# BRD_Board_G1_v53.net
KiCad netlist of a schematic drawn in EAGLE
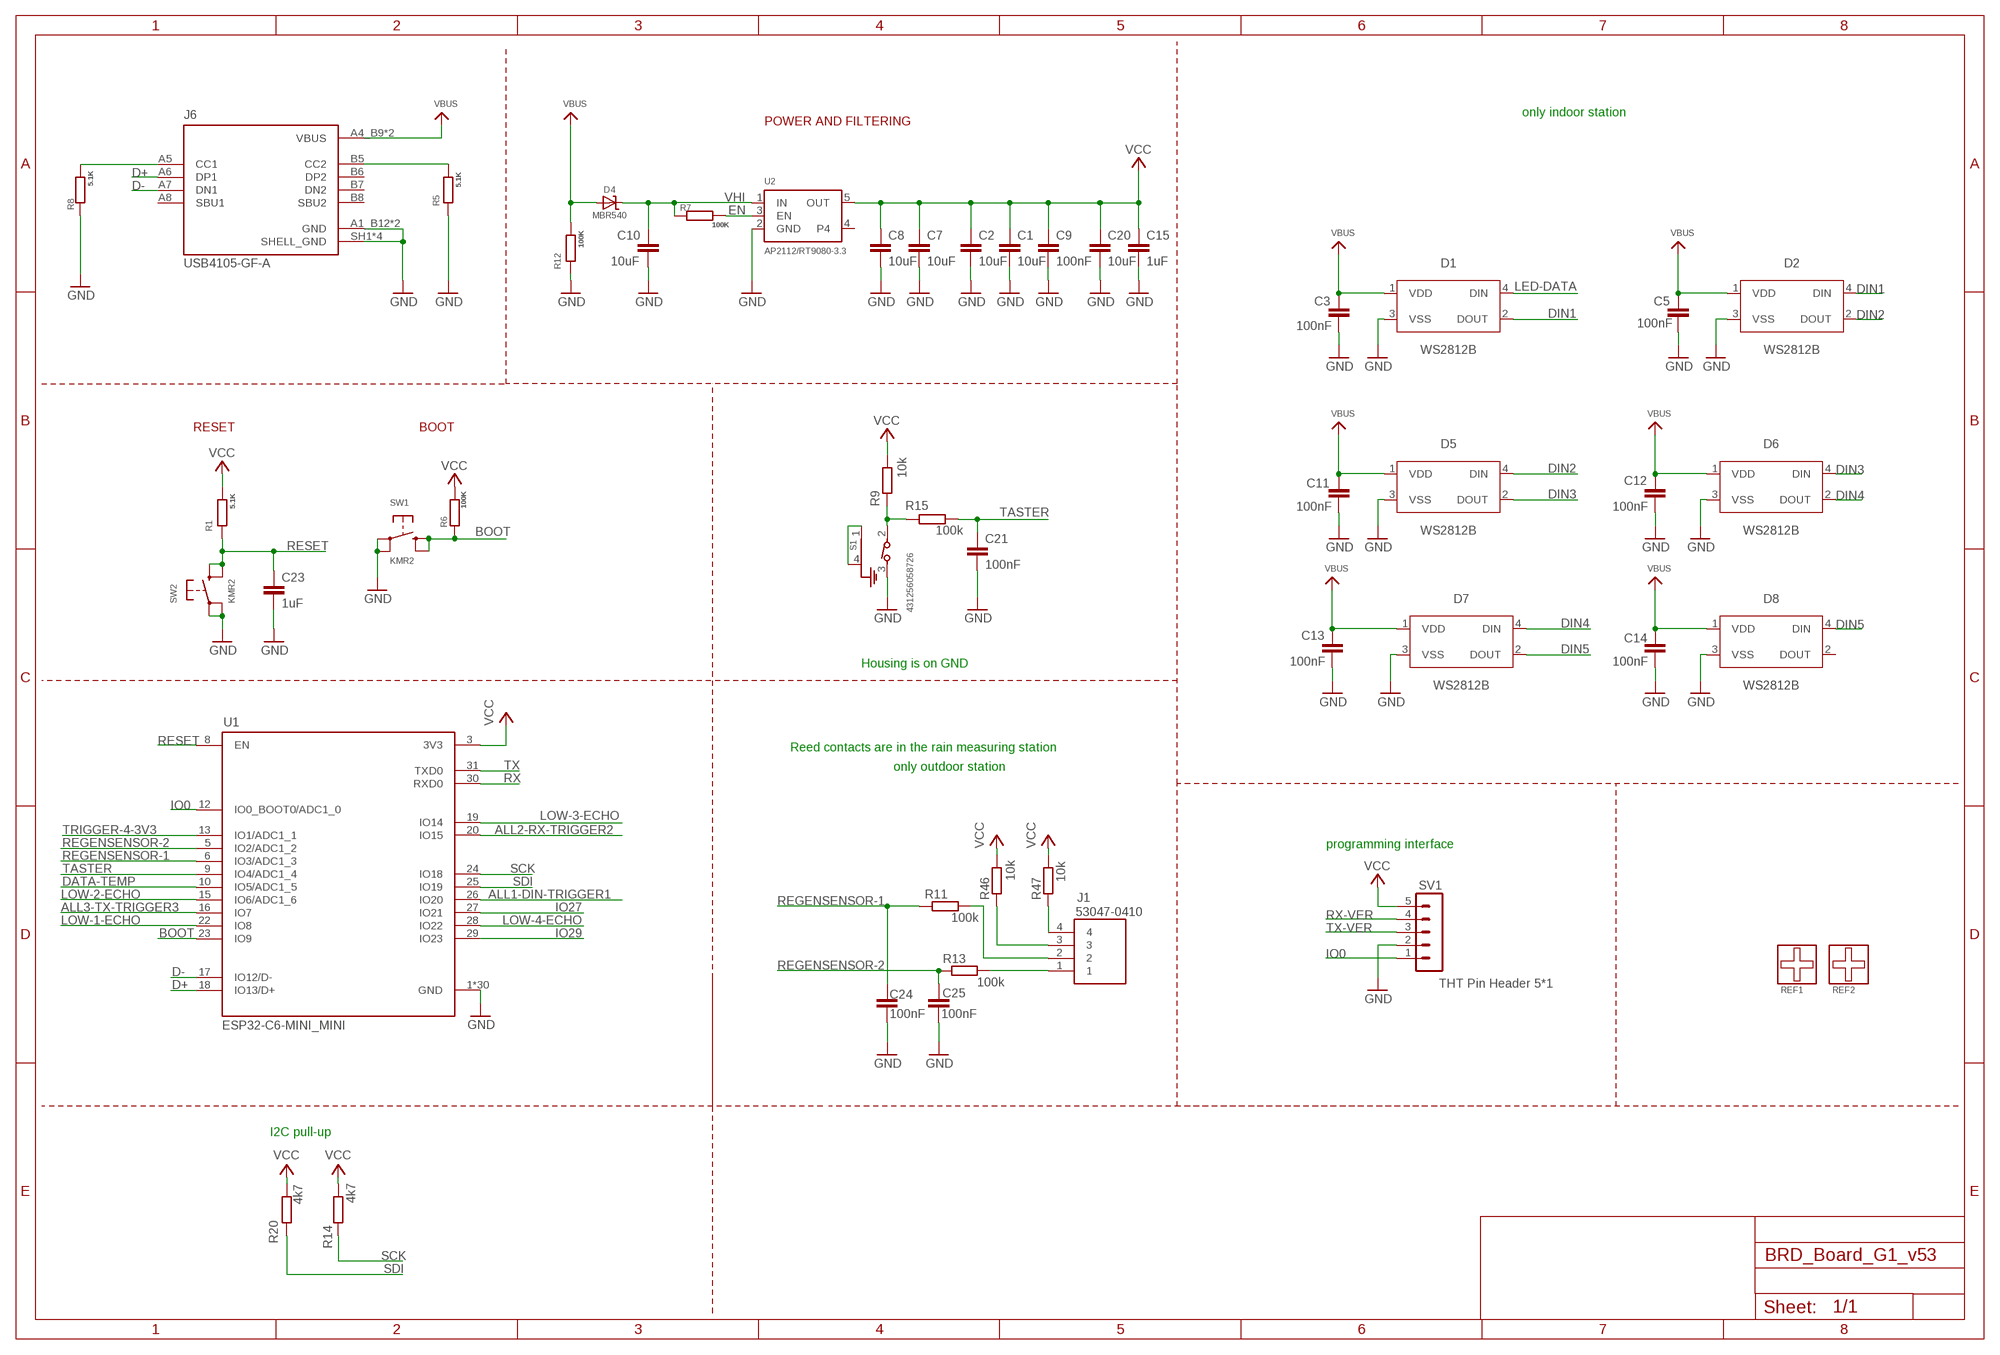
[diagram p0: schematic, sheet 1, part 1 of 2]
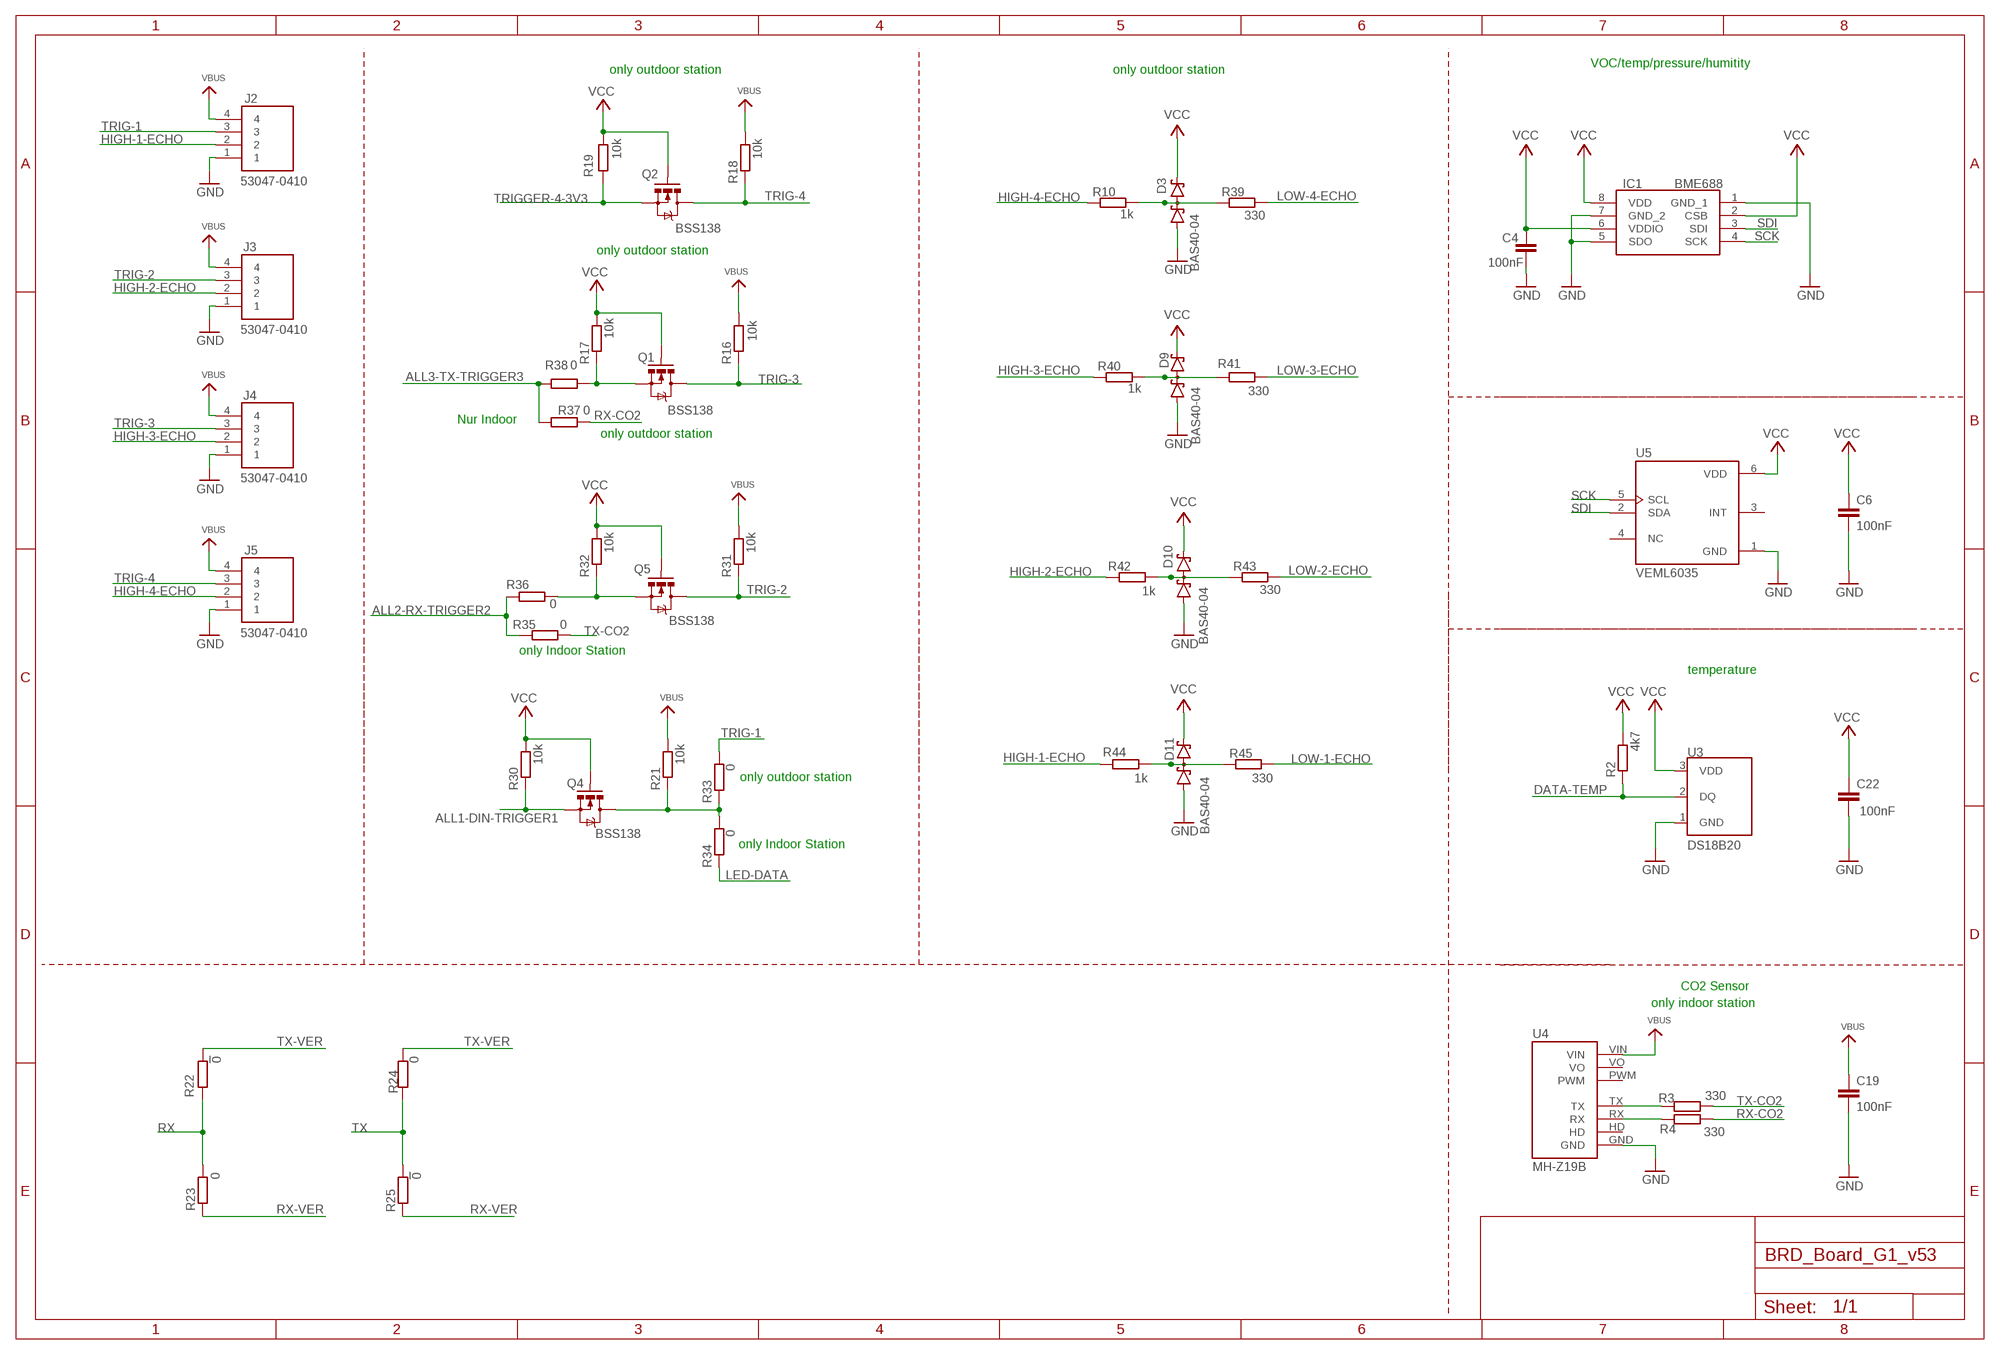
[diagram p1: schematic, sheet 1, part 2 of 2]

(export (version "E")
  (design (tool "Eeschema 10.0.6"))
  (components
    (comp (ref "C1")
      (value "10uF")
      (footprint "eagle-import:C0805K")
      (libsource (lib "eagle-import") (part "C-EUC0805K"))
    )
    (comp (ref "C2")
      (value "10uF")
      (footprint "eagle-import:C0805K")
      (libsource (lib "eagle-import") (part "C-EUC0805K"))
    )
    (comp (ref "C3")
      (value "100nF")
      (footprint "eagle-import:C0603K")
      (libsource (lib "eagle-import") (part "C-EUC0603K"))
    )
    (comp (ref "C4")
      (value "100nF")
      (footprint "eagle-import:C0603K")
      (libsource (lib "eagle-import") (part "C-EUC0603K"))
    )
    (comp (ref "C5")
      (value "100nF")
      (footprint "eagle-import:C0603K")
      (libsource (lib "eagle-import") (part "C-EUC0603K"))
    )
    (comp (ref "C6")
      (value "100nF")
      (footprint "eagle-import:C0603K")
      (libsource (lib "eagle-import") (part "C-EUC0603K"))
    )
    (comp (ref "C7")
      (value "10uF")
      (footprint "eagle-import:C0805K")
      (libsource (lib "eagle-import") (part "C-EUC0805K"))
    )
    (comp (ref "C8")
      (value "10uF")
      (footprint "eagle-import:C0805K")
      (libsource (lib "eagle-import") (part "C-EUC0805K"))
    )
    (comp (ref "C9")
      (value "100nF")
      (footprint "eagle-import:C0603K")
      (libsource (lib "eagle-import") (part "C-EUC0603K"))
    )
    (comp (ref "C10")
      (value "10uF")
      (footprint "eagle-import:C0805K")
      (libsource (lib "eagle-import") (part "C-EUC0805K"))
    )
    (comp (ref "C11")
      (value "100nF")
      (footprint "eagle-import:C0603K")
      (libsource (lib "eagle-import") (part "C-EUC0603K"))
    )
    (comp (ref "C12")
      (value "100nF")
      (footprint "eagle-import:C0603K")
      (libsource (lib "eagle-import") (part "C-EUC0603K"))
    )
    (comp (ref "C13")
      (value "100nF")
      (footprint "eagle-import:C0603K")
      (libsource (lib "eagle-import") (part "C-EUC0603K"))
    )
    (comp (ref "C14")
      (value "100nF")
      (footprint "eagle-import:C0603K")
      (libsource (lib "eagle-import") (part "C-EUC0603K"))
    )
    (comp (ref "C15")
      (value "1uF")
      (footprint "eagle-import:C0603K")
      (libsource (lib "eagle-import") (part "C-EUC0603K"))
    )
    (comp (ref "C19")
      (value "100nF")
      (footprint "eagle-import:C0603K")
      (libsource (lib "eagle-import") (part "C-EUC0603K"))
    )
    (comp (ref "C20")
      (value "10uF")
      (footprint "eagle-import:C0805K")
      (libsource (lib "eagle-import") (part "C-EUC0805K"))
    )
    (comp (ref "C21")
      (value "100nF")
      (footprint "eagle-import:C0603K")
      (libsource (lib "eagle-import") (part "C-EUC0603K"))
    )
    (comp (ref "C22")
      (value "100nF")
      (footprint "eagle-import:C0603K")
      (libsource (lib "eagle-import") (part "C-EUC0603K"))
    )
    (comp (ref "C23")
      (value "1uF")
      (footprint "eagle-import:C0805K")
      (libsource (lib "eagle-import") (part "C-EUC0805K"))
    )
    (comp (ref "C24")
      (value "100nF")
      (footprint "eagle-import:C0603K")
      (libsource (lib "eagle-import") (part "C-EUC0603K"))
    )
    (comp (ref "C25")
      (value "100nF")
      (footprint "eagle-import:C0603K")
      (libsource (lib "eagle-import") (part "C-EUC0603K"))
    )
    (comp (ref "D1")
      (value "WS2812B")
      (footprint "eagle-import:WS2812B")
      (fields (field (name "MANUFACTURER") "Worldsemi"))
      (libsource (lib "eagle-import") (part "WS2812B"))
    )
    (comp (ref "D2")
      (value "WS2812B")
      (footprint "eagle-import:WS2812B")
      (fields (field (name "MANUFACTURER") "Worldsemi"))
      (libsource (lib "eagle-import") (part "WS2812B"))
    )
    (comp (ref "D3")
      (value "BAS40-04")
      (footprint "eagle-import:SOT23")
      (libsource (lib "eagle-import") (part "BAS40-04"))
    )
    (comp (ref "D4")
      (value "MBR540")
      (footprint "eagle-import:SOD-123")
      (libsource (lib "eagle-import") (part "DIODE-SCHOTTKYSOD-123"))
    )
    (comp (ref "D5")
      (value "WS2812B")
      (footprint "eagle-import:WS2812B")
      (fields (field (name "MANUFACTURER") "Worldsemi"))
      (libsource (lib "eagle-import") (part "WS2812B"))
    )
    (comp (ref "D6")
      (value "WS2812B")
      (footprint "eagle-import:WS2812B")
      (fields (field (name "MANUFACTURER") "Worldsemi"))
      (libsource (lib "eagle-import") (part "WS2812B"))
    )
    (comp (ref "D7")
      (value "WS2812B")
      (footprint "eagle-import:WS2812B")
      (fields (field (name "MANUFACTURER") "Worldsemi"))
      (libsource (lib "eagle-import") (part "WS2812B"))
    )
    (comp (ref "D8")
      (value "WS2812B")
      (footprint "eagle-import:WS2812B")
      (fields (field (name "MANUFACTURER") "Worldsemi"))
      (libsource (lib "eagle-import") (part "WS2812B"))
    )
    (comp (ref "D9")
      (value "BAS40-04")
      (footprint "eagle-import:SOT23")
      (libsource (lib "eagle-import") (part "BAS40-04"))
    )
    (comp (ref "D10")
      (value "BAS40-04")
      (footprint "eagle-import:SOT23")
      (libsource (lib "eagle-import") (part "BAS40-04"))
    )
    (comp (ref "D11")
      (value "BAS40-04")
      (footprint "eagle-import:SOT23")
      (libsource (lib "eagle-import") (part "BAS40-04"))
    )
    (comp (ref "IC1")
      (value "BME688")
      (footprint "eagle-import:BME688")
      (fields (field (name "MOUSER_PART_NUMBER") "262-BME688"))
      (libsource (lib "eagle-import") (part "BME688"))
    )
    (comp (ref "J1")
      (value "53047-0410")
      (footprint "eagle-import:530470410")
      (fields (field (name "MOUSER_PART_NUMBER") "538-53047-0410"))
      (libsource (lib "eagle-import") (part "53047-0410"))
    )
    (comp (ref "J2")
      (value "53047-0410")
      (footprint "eagle-import:530470410")
      (fields (field (name "MOUSER_PART_NUMBER") "538-53047-0410"))
      (libsource (lib "eagle-import") (part "53047-0410"))
    )
    (comp (ref "J3")
      (value "53047-0410")
      (footprint "eagle-import:530470410")
      (fields (field (name "MOUSER_PART_NUMBER") "538-53047-0410"))
      (libsource (lib "eagle-import") (part "53047-0410"))
    )
    (comp (ref "J4")
      (value "53047-0410")
      (footprint "eagle-import:530470410")
      (fields (field (name "MOUSER_PART_NUMBER") "538-53047-0410"))
      (libsource (lib "eagle-import") (part "53047-0410"))
    )
    (comp (ref "J5")
      (value "53047-0410")
      (footprint "eagle-import:530470410")
      (fields (field (name "MOUSER_PART_NUMBER") "538-53047-0410"))
      (libsource (lib "eagle-import") (part "53047-0410"))
    )
    (comp (ref "J6")
      (value "USB4105-GF-A")
      (footprint "eagle-import:GCT_USB4105-GF-A")
      (fields (field (name "MF") "GCT"))
      (libsource (lib "eagle-import") (part "USB4105-GF-A"))
    )
    (comp (ref "Q1")
      (value "BSS138")
      (footprint "eagle-import:SOT23")
      (libsource (lib "eagle-import") (part "MOSFET-NCHANNELBSS138"))
    )
    (comp (ref "Q2")
      (value "BSS138")
      (footprint "eagle-import:SOT23")
      (libsource (lib "eagle-import") (part "MOSFET-NCHANNELBSS138"))
    )
    (comp (ref "Q4")
      (value "BSS138")
      (footprint "eagle-import:SOT23")
      (libsource (lib "eagle-import") (part "MOSFET-NCHANNELBSS138"))
    )
    (comp (ref "Q5")
      (value "BSS138")
      (footprint "eagle-import:SOT23")
      (libsource (lib "eagle-import") (part "MOSFET-NCHANNELBSS138"))
    )
    (comp (ref "R1")
      (value "5.1K")
      (footprint "eagle-import:R0805")
      (libsource (lib "eagle-import") (part "R-EU_R0805"))
    )
    (comp (ref "R2")
      (value "4k7")
      (footprint "eagle-import:R0805")
      (libsource (lib "eagle-import") (part "R-EU_R0805"))
    )
    (comp (ref "R3")
      (value "330")
      (footprint "eagle-import:R0805")
      (libsource (lib "eagle-import") (part "R-EU_R0805"))
    )
    (comp (ref "R4")
      (value "330")
      (footprint "eagle-import:R0805")
      (libsource (lib "eagle-import") (part "R-EU_R0805"))
    )
    (comp (ref "R5")
      (value "5.1K")
      (footprint "eagle-import:R0805")
      (libsource (lib "eagle-import") (part "R-EU_R0805"))
    )
    (comp (ref "R6")
      (value "100K")
      (footprint "eagle-import:R0805")
      (libsource (lib "eagle-import") (part "R-EU_R0805"))
    )
    (comp (ref "R7")
      (value "100K")
      (footprint "eagle-import:R0805")
      (libsource (lib "eagle-import") (part "R-EU_R0805"))
    )
    (comp (ref "R8")
      (value "5.1K")
      (footprint "eagle-import:R0805")
      (libsource (lib "eagle-import") (part "R-EU_R0805"))
    )
    (comp (ref "R9")
      (value "10k")
      (footprint "eagle-import:R0805")
      (libsource (lib "eagle-import") (part "R-EU_R0805"))
    )
    (comp (ref "R10")
      (value "1k")
      (footprint "eagle-import:R0805")
      (libsource (lib "eagle-import") (part "R-EU_R0805"))
    )
    (comp (ref "R11")
      (value "100k")
      (footprint "eagle-import:R0805")
      (libsource (lib "eagle-import") (part "R-EU_R0805"))
    )
    (comp (ref "R12")
      (value "100K")
      (footprint "eagle-import:R0805")
      (libsource (lib "eagle-import") (part "R-EU_R0805"))
    )
    (comp (ref "R13")
      (value "100k")
      (footprint "eagle-import:R0805")
      (libsource (lib "eagle-import") (part "R-EU_R0805"))
    )
    (comp (ref "R14")
      (value "4k7")
      (footprint "eagle-import:R0805")
      (libsource (lib "eagle-import") (part "R-EU_R0805"))
    )
    (comp (ref "R15")
      (value "100k")
      (footprint "eagle-import:R0805")
      (libsource (lib "eagle-import") (part "R-EU_R0805"))
    )
    (comp (ref "R16")
      (value "10k")
      (footprint "eagle-import:R0805")
      (libsource (lib "eagle-import") (part "R-EU_R0805"))
    )
    (comp (ref "R17")
      (value "10k")
      (footprint "eagle-import:R0805")
      (libsource (lib "eagle-import") (part "R-EU_R0805"))
    )
    (comp (ref "R18")
      (value "10k")
      (footprint "eagle-import:R0805")
      (libsource (lib "eagle-import") (part "R-EU_R0805"))
    )
    (comp (ref "R19")
      (value "10k")
      (footprint "eagle-import:R0805")
      (libsource (lib "eagle-import") (part "R-EU_R0805"))
    )
    (comp (ref "R20")
      (value "4k7")
      (footprint "eagle-import:R0805")
      (libsource (lib "eagle-import") (part "R-EU_R0805"))
    )
    (comp (ref "R21")
      (value "10k")
      (footprint "eagle-import:R0805")
      (libsource (lib "eagle-import") (part "R-EU_R0805"))
    )
    (comp (ref "R22")
      (value "!0")
      (footprint "eagle-import:R0805")
      (libsource (lib "eagle-import") (part "R-EU_R0805"))
    )
    (comp (ref "R23")
      (value "0")
      (footprint "eagle-import:R0805")
      (libsource (lib "eagle-import") (part "R-EU_R0805"))
    )
    (comp (ref "R24")
      (value "0")
      (footprint "eagle-import:R0805")
      (libsource (lib "eagle-import") (part "R-EU_R0805"))
    )
    (comp (ref "R25")
      (value "!0")
      (footprint "eagle-import:R0805")
      (libsource (lib "eagle-import") (part "R-EU_R0805"))
    )
    (comp (ref "R30")
      (value "10k")
      (footprint "eagle-import:R0805")
      (libsource (lib "eagle-import") (part "R-EU_R0805"))
    )
    (comp (ref "R31")
      (value "10k")
      (footprint "eagle-import:R0805")
      (libsource (lib "eagle-import") (part "R-EU_R0805"))
    )
    (comp (ref "R32")
      (value "10k")
      (footprint "eagle-import:R0805")
      (libsource (lib "eagle-import") (part "R-EU_R0805"))
    )
    (comp (ref "R33")
      (value "0")
      (footprint "eagle-import:R0805")
      (libsource (lib "eagle-import") (part "R-EU_R0805"))
    )
    (comp (ref "R34")
      (value "0")
      (footprint "eagle-import:R0805")
      (libsource (lib "eagle-import") (part "R-EU_R0805"))
    )
    (comp (ref "R35")
      (value "0")
      (footprint "eagle-import:R0805")
      (libsource (lib "eagle-import") (part "R-EU_R0805"))
    )
    (comp (ref "R36")
      (value "0")
      (footprint "eagle-import:R0805")
      (libsource (lib "eagle-import") (part "R-EU_R0805"))
    )
    (comp (ref "R37")
      (value "0")
      (footprint "eagle-import:R0805")
      (libsource (lib "eagle-import") (part "R-EU_R0805"))
    )
    (comp (ref "R38")
      (value "0")
      (footprint "eagle-import:R0805")
      (libsource (lib "eagle-import") (part "R-EU_R0805"))
    )
    (comp (ref "R39")
      (value "330")
      (footprint "eagle-import:R0805")
      (libsource (lib "eagle-import") (part "R-EU_R0805"))
    )
    (comp (ref "R40")
      (value "1k")
      (footprint "eagle-import:R0805")
      (libsource (lib "eagle-import") (part "R-EU_R0805"))
    )
    (comp (ref "R41")
      (value "330")
      (footprint "eagle-import:R0805")
      (libsource (lib "eagle-import") (part "R-EU_R0805"))
    )
    (comp (ref "R42")
      (value "1k")
      (footprint "eagle-import:R0805")
      (libsource (lib "eagle-import") (part "R-EU_R0805"))
    )
    (comp (ref "R43")
      (value "330")
      (footprint "eagle-import:R0805")
      (libsource (lib "eagle-import") (part "R-EU_R0805"))
    )
    (comp (ref "R44")
      (value "1k")
      (footprint "eagle-import:R0805")
      (libsource (lib "eagle-import") (part "R-EU_R0805"))
    )
    (comp (ref "R45")
      (value "330")
      (footprint "eagle-import:R0805")
      (libsource (lib "eagle-import") (part "R-EU_R0805"))
    )
    (comp (ref "R46")
      (value "10k")
      (footprint "eagle-import:R0805")
      (libsource (lib "eagle-import") (part "R-EU_R0805"))
    )
    (comp (ref "R47")
      (value "10k")
      (footprint "eagle-import:R0805")
      (libsource (lib "eagle-import") (part "R-EU_R0805"))
    )
    (comp (ref "REF1")
      (value "FIDUCIALFIDU_1_3_MM")
      (footprint "eagle-import:FIDU_1_3MM")
      (libsource (lib "eagle-import") (part "FIDUCIALFIDU_1_3_MM"))
    )
    (comp (ref "REF2")
      (value "FIDUCIALFIDU_1_3_MM")
      (footprint "eagle-import:FIDU_1_3MM")
      (libsource (lib "eagle-import") (part "FIDUCIALFIDU_1_3_MM"))
    )
    (comp (ref "S1")
      (value "431256058726")
      (footprint "eagle-import:4312560587X6")
      (fields (field (name "MF") "Würth Elektronik") (field (name "MP") "431256058716"))
      (libsource (lib "eagle-import") (part "431256058726"))
    )
    (comp (ref "SV1")
      (value "THT Pin Header 5*1")
      (footprint "eagle-import:MAR05-1")
      (libsource (lib "eagle-import") (part "MAR05-1"))
    )
    (comp (ref "SW1")
      (value "KMR2")
      (footprint "eagle-import:BTN_RKB2_4.6X2.8")
      (libsource (lib "eagle-import") (part "SWITCH_TACT_SMT_RKB2"))
    )
    (comp (ref "SW2")
      (value "KMR2")
      (footprint "eagle-import:BTN_RKB2_4.6X2.8")
      (libsource (lib "eagle-import") (part "SWITCH_TACT_SMT_RKB2"))
    )
    (comp (ref "U1")
      (value "ESP32-C6-MINI_MINI")
      (footprint "eagle-import:ESP32-PICO-MINI")
      (libsource (lib "eagle-import") (part "ESP32-C6-MINI_MINI"))
    )
    (comp (ref "U2")
      (value "AP2112/RT9080-3.3")
      (footprint "eagle-import:SOT23-5")
      (fields (field (name "JLC_ROTATION") "0"))
      (libsource (lib "eagle-import") (part "VREG_SOT23-5"))
    )
    (comp (ref "U3")
      (value "DS18B20")
      (footprint "eagle-import:TO-92-AMMO")
      (libsource (lib "eagle-import") (part "DS18B20"))
    )
    (comp (ref "U4")
      (value "MH-Z19B")
      (footprint "eagle-import:MH-Z19B")
      (fields (field (name "MF") "Winsen"))
      (libsource (lib "eagle-import") (part "MH-Z19B"))
    )
    (comp (ref "U5")
      (value "VEML6035")
      (footprint "eagle-import:XDCR_VEML6035")
      (fields (field (name "MF") "Vishay Semiconductor Opto Division"))
      (libsource (lib "eagle-import") (part "VEML6035"))
    )
  )
  (nets
    (net (code "1") (name "/ALL1-DIN-TRIGGER1") (class "Default")
      (node (ref "Q4") (pin "2") (pinfunction "S_2") (pintype "passive"))
      (node (ref "R30") (pin "1") (pinfunction "1_1") (pintype "passive"))
      (node (ref "U1") (pin "26") (pinfunction "IO20_26") (pintype "bidirectional"))
    )
    (net (code "2") (name "/ALL2-RX-TRIGGER2") (class "Default")
      (node (ref "R35") (pin "1") (pinfunction "1_1") (pintype "passive"))
      (node (ref "R36") (pin "1") (pinfunction "1_1") (pintype "passive"))
      (node (ref "U1") (pin "20") (pinfunction "IO15_20") (pintype "bidirectional"))
    )
    (net (code "3") (name "/ALL3-TX-TRIGGER3") (class "Default")
      (node (ref "R37") (pin "1") (pinfunction "1_1") (pintype "passive"))
      (node (ref "R38") (pin "1") (pinfunction "1_1") (pintype "passive"))
      (node (ref "U1") (pin "16") (pinfunction "IO7_16") (pintype "bidirectional"))
    )
    (net (code "4") (name "/BOOT") (class "Default")
      (node (ref "R6") (pin "1") (pinfunction "1_1") (pintype "passive"))
      (node (ref "SW1") (pin "B") (pinfunction "S_B") (pintype "passive"))
      (node (ref "SW1") (pin "B'") (pinfunction "S1_B'") (pintype "passive"))
      (node (ref "U1") (pin "23") (pinfunction "IO9_23") (pintype "bidirectional"))
    )
    (net (code "5") (name "/D+") (class "Default")
      (node (ref "J6") (pin "A6") (pinfunction "DP1_A6") (pintype "bidirectional"))
      (node (ref "U1") (pin "18") (pinfunction "IO13/D+_18") (pintype "bidirectional"))
    )
    (net (code "6") (name "/D-") (class "Default")
      (node (ref "J6") (pin "A7") (pinfunction "DN1_A7") (pintype "bidirectional"))
      (node (ref "U1") (pin "17") (pinfunction "IO12/D-_17") (pintype "bidirectional"))
    )
    (net (code "7") (name "/DATA-TEMP") (class "Default")
      (node (ref "R2") (pin "1") (pinfunction "1_1") (pintype "passive"))
      (node (ref "U1") (pin "10") (pinfunction "IO5/ADC1_5_10") (pintype "bidirectional"))
      (node (ref "U3") (pin "2") (pinfunction "DQ_2") (pintype "bidirectional"))
    )
    (net (code "8") (name "/DIN1") (class "Default")
      (node (ref "D1") (pin "2") (pinfunction "DOUT_2") (pintype "output"))
      (node (ref "D2") (pin "4") (pinfunction "DIN_4") (pintype "input"))
    )
    (net (code "9") (name "/DIN2") (class "Default")
      (node (ref "D2") (pin "2") (pinfunction "DOUT_2") (pintype "output"))
      (node (ref "D5") (pin "4") (pinfunction "DIN_4") (pintype "input"))
    )
    (net (code "10") (name "/DIN3") (class "Default")
      (node (ref "D5") (pin "2") (pinfunction "DOUT_2") (pintype "output"))
      (node (ref "D6") (pin "4") (pinfunction "DIN_4") (pintype "input"))
    )
    (net (code "11") (name "/DIN4") (class "Default")
      (node (ref "D6") (pin "2") (pinfunction "DOUT_2") (pintype "output"))
      (node (ref "D7") (pin "4") (pinfunction "DIN_4") (pintype "input"))
    )
    (net (code "12") (name "/DIN5") (class "Default")
      (node (ref "D7") (pin "2") (pinfunction "DOUT_2") (pintype "output"))
      (node (ref "D8") (pin "4") (pinfunction "DIN_4") (pintype "input"))
    )
    (net (code "13") (name "/EN") (class "Default")
      (node (ref "R7") (pin "1") (pinfunction "1_1") (pintype "passive"))
      (node (ref "U2") (pin "3") (pinfunction "EN_3") (pintype "input"))
    )
    (net (code "14") (name "/HIGH-1-ECHO") (class "Default")
      (node (ref "J2") (pin "2") (pinfunction "2_2") (pintype "bidirectional"))
      (node (ref "R44") (pin "2") (pinfunction "2_2") (pintype "passive"))
    )
    (net (code "15") (name "/HIGH-2-ECHO") (class "Default")
      (node (ref "J3") (pin "2") (pinfunction "2_2") (pintype "bidirectional"))
      (node (ref "R42") (pin "2") (pinfunction "2_2") (pintype "passive"))
    )
    (net (code "16") (name "/HIGH-3-ECHO") (class "Default")
      (node (ref "J4") (pin "2") (pinfunction "2_2") (pintype "bidirectional"))
      (node (ref "R40") (pin "2") (pinfunction "2_2") (pintype "passive"))
    )
    (net (code "17") (name "/HIGH-4-ECHO") (class "Default")
      (node (ref "J5") (pin "2") (pinfunction "2_2") (pintype "bidirectional"))
      (node (ref "R10") (pin "2") (pinfunction "2_2") (pintype "passive"))
    )
    (net (code "18") (name "/IO0") (class "Default")
      (node (ref "SV1") (pin "1") (pinfunction "1_1") (pintype "passive"))
      (node (ref "U1") (pin "12") (pinfunction "IO0_BOOT0/ADC1_0_12") (pintype "bidirectional"))
    )
    (net (code "19") (name "/IO27") (class "Default")
      (node (ref "U1") (pin "27") (pinfunction "IO21_27") (pintype "bidirectional"))
    )
    (net (code "20") (name "/IO29") (class "Default")
      (node (ref "U1") (pin "29") (pinfunction "IO23_29") (pintype "bidirectional"))
    )
    (net (code "21") (name "/LED-DATA") (class "Default")
      (node (ref "D1") (pin "4") (pinfunction "DIN_4") (pintype "input"))
      (node (ref "R34") (pin "1") (pinfunction "1_1") (pintype "passive"))
    )
    (net (code "22") (name "/LOW-1-ECHO") (class "Default")
      (node (ref "R45") (pin "1") (pinfunction "1_1") (pintype "passive"))
      (node (ref "U1") (pin "22") (pinfunction "IO8_22") (pintype "bidirectional"))
    )
    (net (code "23") (name "/LOW-2-ECHO") (class "Default")
      (node (ref "R43") (pin "1") (pinfunction "1_1") (pintype "passive"))
      (node (ref "U1") (pin "15") (pinfunction "IO6/ADC1_6_15") (pintype "bidirectional"))
    )
    (net (code "24") (name "/LOW-3-ECHO") (class "Default")
      (node (ref "R41") (pin "1") (pinfunction "1_1") (pintype "passive"))
      (node (ref "U1") (pin "19") (pinfunction "IO14_19") (pintype "bidirectional"))
    )
    (net (code "25") (name "/LOW-4-ECHO") (class "Default")
      (node (ref "R39") (pin "1") (pinfunction "1_1") (pintype "passive"))
      (node (ref "U1") (pin "28") (pinfunction "IO22_28") (pintype "bidirectional"))
    )
    (net (code "26") (name "/REGENSENSOR-1") (class "Default")
      (node (ref "C24") (pin "1") (pinfunction "1_1") (pintype "passive"))
      (node (ref "R11") (pin "2") (pinfunction "2_2") (pintype "passive"))
      (node (ref "U1") (pin "6") (pinfunction "IO3/ADC1_3_6") (pintype "bidirectional"))
    )
    (net (code "27") (name "/REGENSENSOR-2") (class "Default")
      (node (ref "C25") (pin "1") (pinfunction "1_1") (pintype "passive"))
      (node (ref "R13") (pin "2") (pinfunction "2_2") (pintype "passive"))
      (node (ref "U1") (pin "5") (pinfunction "IO2/ADC1_2_5") (pintype "bidirectional"))
    )
    (net (code "28") (name "/RESET") (class "Default")
      (node (ref "C23") (pin "1") (pinfunction "1_1") (pintype "passive"))
      (node (ref "R1") (pin "1") (pinfunction "1_1") (pintype "passive"))
      (node (ref "SW2") (pin "B") (pinfunction "S_B") (pintype "passive"))
      (node (ref "SW2") (pin "B'") (pinfunction "S1_B'") (pintype "passive"))
      (node (ref "U1") (pin "8") (pinfunction "EN_8") (pintype "input"))
    )
    (net (code "29") (name "/RX") (class "Default")
      (node (ref "R22") (pin "2") (pinfunction "2_2") (pintype "passive"))
      (node (ref "R23") (pin "1") (pinfunction "1_1") (pintype "passive"))
      (node (ref "U1") (pin "30") (pinfunction "RXD0_30") (pintype "bidirectional"))
    )
    (net (code "30") (name "/RX-CO2") (class "Default")
      (node (ref "R37") (pin "2") (pinfunction "2_2") (pintype "passive"))
      (node (ref "R4") (pin "1") (pinfunction "1_1") (pintype "passive"))
    )
    (net (code "31") (name "/RX-VER") (class "Default")
      (node (ref "R23") (pin "2") (pinfunction "2_2") (pintype "passive"))
      (node (ref "R25") (pin "2") (pinfunction "2_2") (pintype "passive"))
      (node (ref "SV1") (pin "4") (pinfunction "4_4") (pintype "passive"))
    )
    (net (code "32") (name "/SCK") (class "Default")
      (node (ref "IC1") (pin "4") (pinfunction "SCK_4") (pintype "bidirectional"))
      (node (ref "R14") (pin "1") (pinfunction "1_1") (pintype "passive"))
      (node (ref "U1") (pin "24") (pinfunction "IO18_24") (pintype "bidirectional"))
      (node (ref "U5") (pin "5") (pinfunction "SCL_5") (pintype "input"))
    )
    (net (code "33") (name "/SDI") (class "Default")
      (node (ref "IC1") (pin "3") (pinfunction "SDI_3") (pintype "bidirectional"))
      (node (ref "R20") (pin "1") (pinfunction "1_1") (pintype "passive"))
      (node (ref "U1") (pin "25") (pinfunction "IO19_25") (pintype "bidirectional"))
      (node (ref "U5") (pin "2") (pinfunction "SDA_2") (pintype "bidirectional"))
    )
    (net (code "34") (name "/TASTER") (class "Default")
      (node (ref "C21") (pin "1") (pinfunction "1_1") (pintype "passive"))
      (node (ref "R15") (pin "1") (pinfunction "1_1") (pintype "passive"))
      (node (ref "U1") (pin "9") (pinfunction "IO4/ADC1_4_9") (pintype "bidirectional"))
    )
    (net (code "35") (name "/TRIG-1") (class "Default")
      (node (ref "J2") (pin "3") (pinfunction "3_3") (pintype "bidirectional"))
      (node (ref "R33") (pin "2") (pinfunction "2_2") (pintype "passive"))
    )
    (net (code "36") (name "/TRIG-2") (class "Default")
      (node (ref "J3") (pin "3") (pinfunction "3_3") (pintype "bidirectional"))
      (node (ref "Q5") (pin "3") (pinfunction "D_3") (pintype "passive"))
      (node (ref "R31") (pin "1") (pinfunction "1_1") (pintype "passive"))
    )
    (net (code "37") (name "/TRIG-3") (class "Default")
      (node (ref "J4") (pin "3") (pinfunction "3_3") (pintype "bidirectional"))
      (node (ref "Q1") (pin "3") (pinfunction "D_3") (pintype "passive"))
      (node (ref "R16") (pin "1") (pinfunction "1_1") (pintype "passive"))
    )
    (net (code "38") (name "/TRIG-4") (class "Default")
      (node (ref "J5") (pin "3") (pinfunction "3_3") (pintype "bidirectional"))
      (node (ref "Q2") (pin "3") (pinfunction "D_3") (pintype "passive"))
      (node (ref "R18") (pin "1") (pinfunction "1_1") (pintype "passive"))
    )
    (net (code "39") (name "/TRIGGER-4-3V3") (class "Default")
      (node (ref "Q2") (pin "2") (pinfunction "S_2") (pintype "passive"))
      (node (ref "R19") (pin "1") (pinfunction "1_1") (pintype "passive"))
      (node (ref "U1") (pin "13") (pinfunction "IO1/ADC1_1_13") (pintype "bidirectional"))
    )
    (net (code "40") (name "/TX") (class "Default")
      (node (ref "R24") (pin "2") (pinfunction "2_2") (pintype "passive"))
      (node (ref "R25") (pin "1") (pinfunction "1_1") (pintype "passive"))
      (node (ref "U1") (pin "31") (pinfunction "TXD0_31") (pintype "bidirectional"))
    )
    (net (code "41") (name "/TX-CO2") (class "Default")
      (node (ref "R3") (pin "1") (pinfunction "1_1") (pintype "passive"))
      (node (ref "R35") (pin "2") (pinfunction "2_2") (pintype "passive"))
    )
    (net (code "42") (name "/TX-VER") (class "Default")
      (node (ref "R22") (pin "1") (pinfunction "1_1") (pintype "passive"))
      (node (ref "R24") (pin "1") (pinfunction "1_1") (pintype "passive"))
      (node (ref "SV1") (pin "3") (pinfunction "3_3") (pintype "passive"))
    )
    (net (code "43") (name "/VHI") (class "Default")
      (node (ref "C10") (pin "1") (pinfunction "1_1") (pintype "passive"))
      (node (ref "D4") (pin "C") (pinfunction "C_C") (pintype "passive"))
      (node (ref "R7") (pin "2") (pinfunction "2_2") (pintype "passive"))
      (node (ref "U2") (pin "1") (pinfunction "IN_1") (pintype "power_in"))
    )
    (net (code "44") (name "GND") (class "Default")
      (node (ref "C1") (pin "2") (pinfunction "2_2") (pintype "passive"))
      (node (ref "C10") (pin "2") (pinfunction "2_2") (pintype "passive"))
      (node (ref "C11") (pin "2") (pinfunction "2_2") (pintype "passive"))
      (node (ref "C12") (pin "2") (pinfunction "2_2") (pintype "passive"))
      (node (ref "C13") (pin "2") (pinfunction "2_2") (pintype "passive"))
      (node (ref "C14") (pin "2") (pinfunction "2_2") (pintype "passive"))
      (node (ref "C15") (pin "2") (pinfunction "2_2") (pintype "passive"))
      (node (ref "C19") (pin "2") (pinfunction "2_2") (pintype "passive"))
      (node (ref "C2") (pin "2") (pinfunction "2_2") (pintype "passive"))
      (node (ref "C20") (pin "2") (pinfunction "2_2") (pintype "passive"))
      (node (ref "C21") (pin "2") (pinfunction "2_2") (pintype "passive"))
      (node (ref "C22") (pin "1") (pinfunction "1_1") (pintype "passive"))
      (node (ref "C23") (pin "2") (pinfunction "2_2") (pintype "passive"))
      (node (ref "C24") (pin "2") (pinfunction "2_2") (pintype "passive"))
      (node (ref "C25") (pin "2") (pinfunction "2_2") (pintype "passive"))
      (node (ref "C3") (pin "2") (pinfunction "2_2") (pintype "passive"))
      (node (ref "C4") (pin "1") (pinfunction "1_1") (pintype "passive"))
      (node (ref "C5") (pin "2") (pinfunction "2_2") (pintype "passive"))
      (node (ref "C6") (pin "2") (pinfunction "2_2") (pintype "passive"))
      (node (ref "C7") (pin "2") (pinfunction "2_2") (pintype "passive"))
      (node (ref "C8") (pin "2") (pinfunction "2_2") (pintype "passive"))
      (node (ref "C9") (pin "2") (pinfunction "2_2") (pintype "passive"))
      (node (ref "D1") (pin "3") (pinfunction "VSS_3") (pintype "power_in"))
      (node (ref "D10") (pin "1") (pinfunction "A1_1") (pintype "passive"))
      (node (ref "D11") (pin "1") (pinfunction "A1_1") (pintype "passive"))
      (node (ref "D2") (pin "3") (pinfunction "VSS_3") (pintype "power_in"))
      (node (ref "D3") (pin "1") (pinfunction "A1_1") (pintype "passive"))
      (node (ref "D5") (pin "3") (pinfunction "VSS_3") (pintype "power_in"))
      (node (ref "D6") (pin "3") (pinfunction "VSS_3") (pintype "power_in"))
      (node (ref "D7") (pin "3") (pinfunction "VSS_3") (pintype "power_in"))
      (node (ref "D8") (pin "3") (pinfunction "VSS_3") (pintype "power_in"))
      (node (ref "D9") (pin "1") (pinfunction "A1_1") (pintype "passive"))
      (node (ref "IC1") (pin "1") (pinfunction "GND_1_1") (pintype "bidirectional"))
      (node (ref "IC1") (pin "5") (pinfunction "SDO_5") (pintype "bidirectional"))
      (node (ref "IC1") (pin "7") (pinfunction "GND_2_7") (pintype "bidirectional"))
      (node (ref "J2") (pin "1") (pinfunction "1_1") (pintype "bidirectional"))
      (node (ref "J3") (pin "1") (pinfunction "1_1") (pintype "bidirectional"))
      (node (ref "J4") (pin "1") (pinfunction "1_1") (pintype "bidirectional"))
      (node (ref "J5") (pin "1") (pinfunction "1_1") (pintype "bidirectional"))
      (node (ref "J6") (pin "A1_B12") (pinfunction "GND_A1_B12") (pintype "power_in"))
      (node (ref "J6") (pin "B1_A12") (pinfunction "GND_B1_A12") (pintype "power_in"))
      (node (ref "J6") (pin "SH1") (pinfunction "SHELL_GND_SH1") (pintype "power_in"))
      (node (ref "J6") (pin "SH2") (pinfunction "SHELL_GND_SH2") (pintype "power_in"))
      (node (ref "J6") (pin "SH3") (pinfunction "SHELL_GND_SH3") (pintype "power_in"))
      (node (ref "J6") (pin "SH4") (pinfunction "SHELL_GND_SH4") (pintype "power_in"))
      (node (ref "R12") (pin "1") (pinfunction "1_1") (pintype "passive"))
      (node (ref "R5") (pin "1") (pinfunction "1_1") (pintype "passive"))
      (node (ref "R8") (pin "1") (pinfunction "1_1") (pintype "passive"))
      (node (ref "S1") (pin "3") (pinfunction "3_3") (pintype "passive"))
      (node (ref "SV1") (pin "2") (pinfunction "2_2") (pintype "passive"))
      (node (ref "SW1") (pin "A") (pinfunction "P_A") (pintype "passive"))
      (node (ref "SW1") (pin "A'") (pinfunction "P1_A'") (pintype "passive"))
      (node (ref "SW2") (pin "A") (pinfunction "P_A") (pintype "passive"))
      (node (ref "SW2") (pin "A'") (pinfunction "P1_A'") (pintype "passive"))
      (node (ref "U1") (pin "1") (pinfunction "GND_1") (pintype "power_in"))
      (node (ref "U1") (pin "11") (pinfunction "GND_11") (pintype "power_in"))
      (node (ref "U1") (pin "14") (pinfunction "GND_14") (pintype "power_in"))
      (node (ref "U1") (pin "2") (pinfunction "GND_2") (pintype "power_in"))
      (node (ref "U1") (pin "36") (pinfunction "GND_36") (pintype "power_in"))
      (node (ref "U1") (pin "37") (pinfunction "GND_37") (pintype "power_in"))
      (node (ref "U1") (pin "38") (pinfunction "GND_38") (pintype "power_in"))
      (node (ref "U1") (pin "39") (pinfunction "GND_39") (pintype "power_in"))
      (node (ref "U1") (pin "40") (pinfunction "GND_40") (pintype "power_in"))
      (node (ref "U1") (pin "41") (pinfunction "GND_41") (pintype "power_in"))
      (node (ref "U1") (pin "42") (pinfunction "GND_42") (pintype "power_in"))
      (node (ref "U1") (pin "43") (pinfunction "GND_43") (pintype "power_in"))
      (node (ref "U1") (pin "44") (pinfunction "GND_44") (pintype "power_in"))
      (node (ref "U1") (pin "45") (pinfunction "GND_45") (pintype "power_in"))
      (node (ref "U1") (pin "46") (pinfunction "GND_46") (pintype "power_in"))
      (node (ref "U1") (pin "47") (pinfunction "GND_47") (pintype "power_in"))
      (node (ref "U1") (pin "48") (pinfunction "GND_48") (pintype "power_in"))
      (node (ref "U1") (pin "49") (pinfunction "GND_49") (pintype "power_in"))
      (node (ref "U1") (pin "50") (pinfunction "GND_50") (pintype "power_in"))
      (node (ref "U1") (pin "51") (pinfunction "GND_51") (pintype "power_in"))
      (node (ref "U1") (pin "52") (pinfunction "GND_52") (pintype "power_in"))
      (node (ref "U1") (pin "53") (pinfunction "GND_53") (pintype "power_in"))
      (node (ref "U1") (pin "54") (pinfunction "GND_54") (pintype "power_in"))
      (node (ref "U1") (pin "55") (pinfunction "GND_55") (pintype "power_in"))
      (node (ref "U1") (pin "56") (pinfunction "GND_56") (pintype "power_in"))
      (node (ref "U1") (pin "57") (pinfunction "GND_57") (pintype "power_in"))
      (node (ref "U1") (pin "58") (pinfunction "GND_58") (pintype "power_in"))
      (node (ref "U1") (pin "59") (pinfunction "GND_59") (pintype "power_in"))
      (node (ref "U1") (pin "60") (pinfunction "GND_60") (pintype "power_in"))
      (node (ref "U1") (pin "61") (pinfunction "GND_61") (pintype "power_in"))
      (node (ref "U2") (pin "2") (pinfunction "GND_2") (pintype "power_in"))
      (node (ref "U3") (pin "1") (pinfunction "GND_1") (pintype "power_in"))
      (node (ref "U4") (pin "GND") (pinfunction "GND_GND") (pintype "bidirectional"))
      (node (ref "U5") (pin "1") (pinfunction "GND_1") (pintype "power_in"))
    )
    (net (code "45") (name "Net-(D3-C1A2)") (class "Default")
      (node (ref "D3") (pin "3") (pinfunction "C1A2_3") (pintype "passive"))
      (node (ref "R10") (pin "1") (pinfunction "1_1") (pintype "passive"))
      (node (ref "R39") (pin "2") (pinfunction "2_2") (pintype "passive"))
    )
    (net (code "46") (name "Net-(D9-C1A2)") (class "Default")
      (node (ref "D9") (pin "3") (pinfunction "C1A2_3") (pintype "passive"))
      (node (ref "R40") (pin "1") (pinfunction "1_1") (pintype "passive"))
      (node (ref "R41") (pin "2") (pinfunction "2_2") (pintype "passive"))
    )
    (net (code "47") (name "Net-(D10-C1A2)") (class "Default")
      (node (ref "D10") (pin "3") (pinfunction "C1A2_3") (pintype "passive"))
      (node (ref "R42") (pin "1") (pinfunction "1_1") (pintype "passive"))
      (node (ref "R43") (pin "2") (pinfunction "2_2") (pintype "passive"))
    )
    (net (code "48") (name "Net-(D11-C1A2)") (class "Default")
      (node (ref "D11") (pin "3") (pinfunction "C1A2_3") (pintype "passive"))
      (node (ref "R44") (pin "1") (pinfunction "1_1") (pintype "passive"))
      (node (ref "R45") (pin "2") (pinfunction "2_2") (pintype "passive"))
    )
    (net (code "49") (name "Net-(J1-Pad1)") (class "Default")
      (node (ref "J1") (pin "1") (pinfunction "1_1") (pintype "bidirectional"))
      (node (ref "R13") (pin "1") (pinfunction "1_1") (pintype "passive"))
    )
    (net (code "50") (name "Net-(J1-Pad2)") (class "Default")
      (node (ref "J1") (pin "2") (pinfunction "2_2") (pintype "bidirectional"))
      (node (ref "R11") (pin "1") (pinfunction "1_1") (pintype "passive"))
    )
    (net (code "51") (name "Net-(J1-Pad3)") (class "Default")
      (node (ref "J1") (pin "3") (pinfunction "3_3") (pintype "bidirectional"))
      (node (ref "R46") (pin "1") (pinfunction "1_1") (pintype "passive"))
    )
    (net (code "52") (name "Net-(J1-Pad4)") (class "Default")
      (node (ref "J1") (pin "4") (pinfunction "4_4") (pintype "bidirectional"))
      (node (ref "R47") (pin "1") (pinfunction "1_1") (pintype "passive"))
    )
    (net (code "53") (name "Net-(J6-CC1)") (class "Default")
      (node (ref "J6") (pin "A5") (pinfunction "CC1_A5") (pintype "bidirectional"))
      (node (ref "R8") (pin "2") (pinfunction "2_2") (pintype "passive"))
    )
    (net (code "54") (name "Net-(J6-CC2)") (class "Default")
      (node (ref "J6") (pin "B5") (pinfunction "CC2_B5") (pintype "bidirectional"))
      (node (ref "R5") (pin "2") (pinfunction "2_2") (pintype "passive"))
    )
    (net (code "55") (name "Net-(Q1-S)") (class "Default")
      (node (ref "Q1") (pin "2") (pinfunction "S_2") (pintype "passive"))
      (node (ref "R17") (pin "1") (pinfunction "1_1") (pintype "passive"))
      (node (ref "R38") (pin "2") (pinfunction "2_2") (pintype "passive"))
    )
    (net (code "56") (name "Net-(Q4-D)") (class "Default")
      (node (ref "Q4") (pin "3") (pinfunction "D_3") (pintype "passive"))
      (node (ref "R21") (pin "1") (pinfunction "1_1") (pintype "passive"))
      (node (ref "R33") (pin "1") (pinfunction "1_1") (pintype "passive"))
      (node (ref "R34") (pin "2") (pinfunction "2_2") (pintype "passive"))
    )
    (net (code "57") (name "Net-(Q5-S)") (class "Default")
      (node (ref "Q5") (pin "2") (pinfunction "S_2") (pintype "passive"))
      (node (ref "R32") (pin "1") (pinfunction "1_1") (pintype "passive"))
      (node (ref "R36") (pin "2") (pinfunction "2_2") (pintype "passive"))
    )
    (net (code "58") (name "Net-(R3-Pad2)") (class "Default")
      (node (ref "R3") (pin "2") (pinfunction "2_2") (pintype "passive"))
      (node (ref "U4") (pin "TX") (pinfunction "TX_TX") (pintype "bidirectional"))
    )
    (net (code "59") (name "Net-(R4-Pad2)") (class "Default")
      (node (ref "R4") (pin "2") (pinfunction "2_2") (pintype "passive"))
      (node (ref "U4") (pin "RX") (pinfunction "RX_RX") (pintype "bidirectional"))
    )
    (net (code "60") (name "Net-(R15-Pad2)") (class "Default")
      (node (ref "R15") (pin "2") (pinfunction "2_2") (pintype "passive"))
      (node (ref "R9") (pin "1") (pinfunction "1_1") (pintype "passive"))
      (node (ref "S1") (pin "2") (pinfunction "2_2") (pintype "passive"))
    )
    (net (code "61") (name "Net-(S1-GND)") (class "Default")
      (node (ref "S1") (pin "1") (pinfunction "GND1_1") (pintype "passive"))
      (node (ref "S1") (pin "4") (pinfunction "GND_4") (pintype "passive"))
    )
    (net (code "62") (name "VBUS") (class "Default")
      (node (ref "C11") (pin "1") (pinfunction "1_1") (pintype "passive"))
      (node (ref "C12") (pin "1") (pinfunction "1_1") (pintype "passive"))
      (node (ref "C13") (pin "1") (pinfunction "1_1") (pintype "passive"))
      (node (ref "C14") (pin "1") (pinfunction "1_1") (pintype "passive"))
      (node (ref "C19") (pin "1") (pinfunction "1_1") (pintype "passive"))
      (node (ref "C3") (pin "1") (pinfunction "1_1") (pintype "passive"))
      (node (ref "C5") (pin "1") (pinfunction "1_1") (pintype "passive"))
      (node (ref "D1") (pin "1") (pinfunction "VDD_1") (pintype "power_in"))
      (node (ref "D2") (pin "1") (pinfunction "VDD_1") (pintype "power_in"))
      (node (ref "D4") (pin "A") (pinfunction "A_A") (pintype "passive"))
      (node (ref "D5") (pin "1") (pinfunction "VDD_1") (pintype "power_in"))
      (node (ref "D6") (pin "1") (pinfunction "VDD_1") (pintype "power_in"))
      (node (ref "D7") (pin "1") (pinfunction "VDD_1") (pintype "power_in"))
      (node (ref "D8") (pin "1") (pinfunction "VDD_1") (pintype "power_in"))
      (node (ref "J2") (pin "4") (pinfunction "4_4") (pintype "bidirectional"))
      (node (ref "J3") (pin "4") (pinfunction "4_4") (pintype "bidirectional"))
      (node (ref "J4") (pin "4") (pinfunction "4_4") (pintype "bidirectional"))
      (node (ref "J5") (pin "4") (pinfunction "4_4") (pintype "bidirectional"))
      (node (ref "J6") (pin "A4_B9") (pinfunction "VBUS_A4_B9") (pintype "power_in"))
      (node (ref "J6") (pin "B4_A9") (pinfunction "VBUS_B4_A9") (pintype "power_in"))
      (node (ref "R12") (pin "2") (pinfunction "2_2") (pintype "passive"))
      (node (ref "R16") (pin "2") (pinfunction "2_2") (pintype "passive"))
      (node (ref "R18") (pin "2") (pinfunction "2_2") (pintype "passive"))
      (node (ref "R21") (pin "2") (pinfunction "2_2") (pintype "passive"))
      (node (ref "R31") (pin "2") (pinfunction "2_2") (pintype "passive"))
      (node (ref "U4") (pin "VIN") (pinfunction "VIN_VIN") (pintype "bidirectional"))
    )
    (net (code "63") (name "VCC") (class "Default")
      (node (ref "C1") (pin "1") (pinfunction "1_1") (pintype "passive"))
      (node (ref "C15") (pin "1") (pinfunction "1_1") (pintype "passive"))
      (node (ref "C2") (pin "1") (pinfunction "1_1") (pintype "passive"))
      (node (ref "C20") (pin "1") (pinfunction "1_1") (pintype "passive"))
      (node (ref "C22") (pin "2") (pinfunction "2_2") (pintype "passive"))
      (node (ref "C4") (pin "2") (pinfunction "2_2") (pintype "passive"))
      (node (ref "C6") (pin "1") (pinfunction "1_1") (pintype "passive"))
      (node (ref "C7") (pin "1") (pinfunction "1_1") (pintype "passive"))
      (node (ref "C8") (pin "1") (pinfunction "1_1") (pintype "passive"))
      (node (ref "C9") (pin "1") (pinfunction "1_1") (pintype "passive"))
      (node (ref "D10") (pin "2") (pinfunction "C2_2") (pintype "passive"))
      (node (ref "D11") (pin "2") (pinfunction "C2_2") (pintype "passive"))
      (node (ref "D3") (pin "2") (pinfunction "C2_2") (pintype "passive"))
      (node (ref "D9") (pin "2") (pinfunction "C2_2") (pintype "passive"))
      (node (ref "IC1") (pin "2") (pinfunction "CSB_2") (pintype "bidirectional"))
      (node (ref "IC1") (pin "6") (pinfunction "VDDIO_6") (pintype "bidirectional"))
      (node (ref "IC1") (pin "8") (pinfunction "VDD_8") (pintype "bidirectional"))
      (node (ref "Q1") (pin "1") (pinfunction "G_1") (pintype "passive"))
      (node (ref "Q2") (pin "1") (pinfunction "G_1") (pintype "passive"))
      (node (ref "Q4") (pin "1") (pinfunction "G_1") (pintype "passive"))
      (node (ref "Q5") (pin "1") (pinfunction "G_1") (pintype "passive"))
      (node (ref "R1") (pin "2") (pinfunction "2_2") (pintype "passive"))
      (node (ref "R14") (pin "2") (pinfunction "2_2") (pintype "passive"))
      (node (ref "R17") (pin "2") (pinfunction "2_2") (pintype "passive"))
      (node (ref "R19") (pin "2") (pinfunction "2_2") (pintype "passive"))
      (node (ref "R2") (pin "2") (pinfunction "2_2") (pintype "passive"))
      (node (ref "R20") (pin "2") (pinfunction "2_2") (pintype "passive"))
      (node (ref "R30") (pin "2") (pinfunction "2_2") (pintype "passive"))
      (node (ref "R32") (pin "2") (pinfunction "2_2") (pintype "passive"))
      (node (ref "R46") (pin "2") (pinfunction "2_2") (pintype "passive"))
      (node (ref "R47") (pin "2") (pinfunction "2_2") (pintype "passive"))
      (node (ref "R6") (pin "2") (pinfunction "2_2") (pintype "passive"))
      (node (ref "R9") (pin "2") (pinfunction "2_2") (pintype "passive"))
      (node (ref "SV1") (pin "5") (pinfunction "5_5") (pintype "passive"))
      (node (ref "U1") (pin "3") (pinfunction "3V3_3") (pintype "power_in"))
      (node (ref "U2") (pin "5") (pinfunction "OUT_5") (pintype "power_in"))
      (node (ref "U3") (pin "3") (pinfunction "VDD_3") (pintype "power_in"))
      (node (ref "U5") (pin "6") (pinfunction "VDD_6") (pintype "power_in"))
    )
    (net (code "64") (name "unconnected-(D8-DOUT-Pad2)") (class "Default")
      (node (ref "D8") (pin "2") (pinfunction "DOUT_2") (pintype "output"))
    )
    (net (code "65") (name "unconnected-(J6-DN2-PadB7)") (class "Default")
      (node (ref "J6") (pin "B7") (pinfunction "DN2_B7") (pintype "bidirectional"))
    )
    (net (code "66") (name "unconnected-(J6-DP2-PadB6)") (class "Default")
      (node (ref "J6") (pin "B6") (pinfunction "DP2_B6") (pintype "bidirectional"))
    )
    (net (code "67") (name "unconnected-(J6-SBU1-PadA8)") (class "Default")
      (node (ref "J6") (pin "A8") (pinfunction "SBU1_A8") (pintype "bidirectional"))
    )
    (net (code "68") (name "unconnected-(J6-SBU2-PadB8)") (class "Default")
      (node (ref "J6") (pin "B8") (pinfunction "SBU2_B8") (pintype "bidirectional"))
    )
    (net (code "69") (name "unconnected-(REF1-PadP$1)") (class "Default")
      (node (ref "REF1") (pin "P$1") (pinfunction "P$1_P$1") (pintype "passive"))
    )
    (net (code "70") (name "unconnected-(REF2-PadP$1)") (class "Default")
      (node (ref "REF2") (pin "P$1") (pinfunction "P$1_P$1") (pintype "passive"))
    )
    (net (code "71") (name "unconnected-(U2-P4-Pad4)") (class "Default")
      (node (ref "U2") (pin "4") (pinfunction "P4_4") (pintype "bidirectional"))
    )
    (net (code "72") (name "unconnected-(U4-PadHD)") (class "Default")
      (node (ref "U4") (pin "HD") (pinfunction "HD_HD") (pintype "bidirectional"))
    )
    (net (code "73") (name "unconnected-(U4-PadPWM)") (class "Default")
      (node (ref "U4") (pin "PWM") (pinfunction "PWM_PWM") (pintype "bidirectional"))
    )
    (net (code "74") (name "unconnected-(U4-PadVO)") (class "Default")
      (node (ref "U4") (pin "VO") (pinfunction "VO_VO") (pintype "bidirectional"))
    )
    (net (code "75") (name "unconnected-(U5-INT-Pad3)") (class "Default")
      (node (ref "U5") (pin "3") (pinfunction "INT_3") (pintype "output"))
    )
    (net (code "76") (name "unconnected-(U5-NC-Pad4)") (class "Default")
      (node (ref "U5") (pin "4") (pinfunction "NC_4") (pintype "no_connect"))
    )
  )
)
